# thermokoppel.net
KiCad netlist of a schematic drawn in Altium Designer
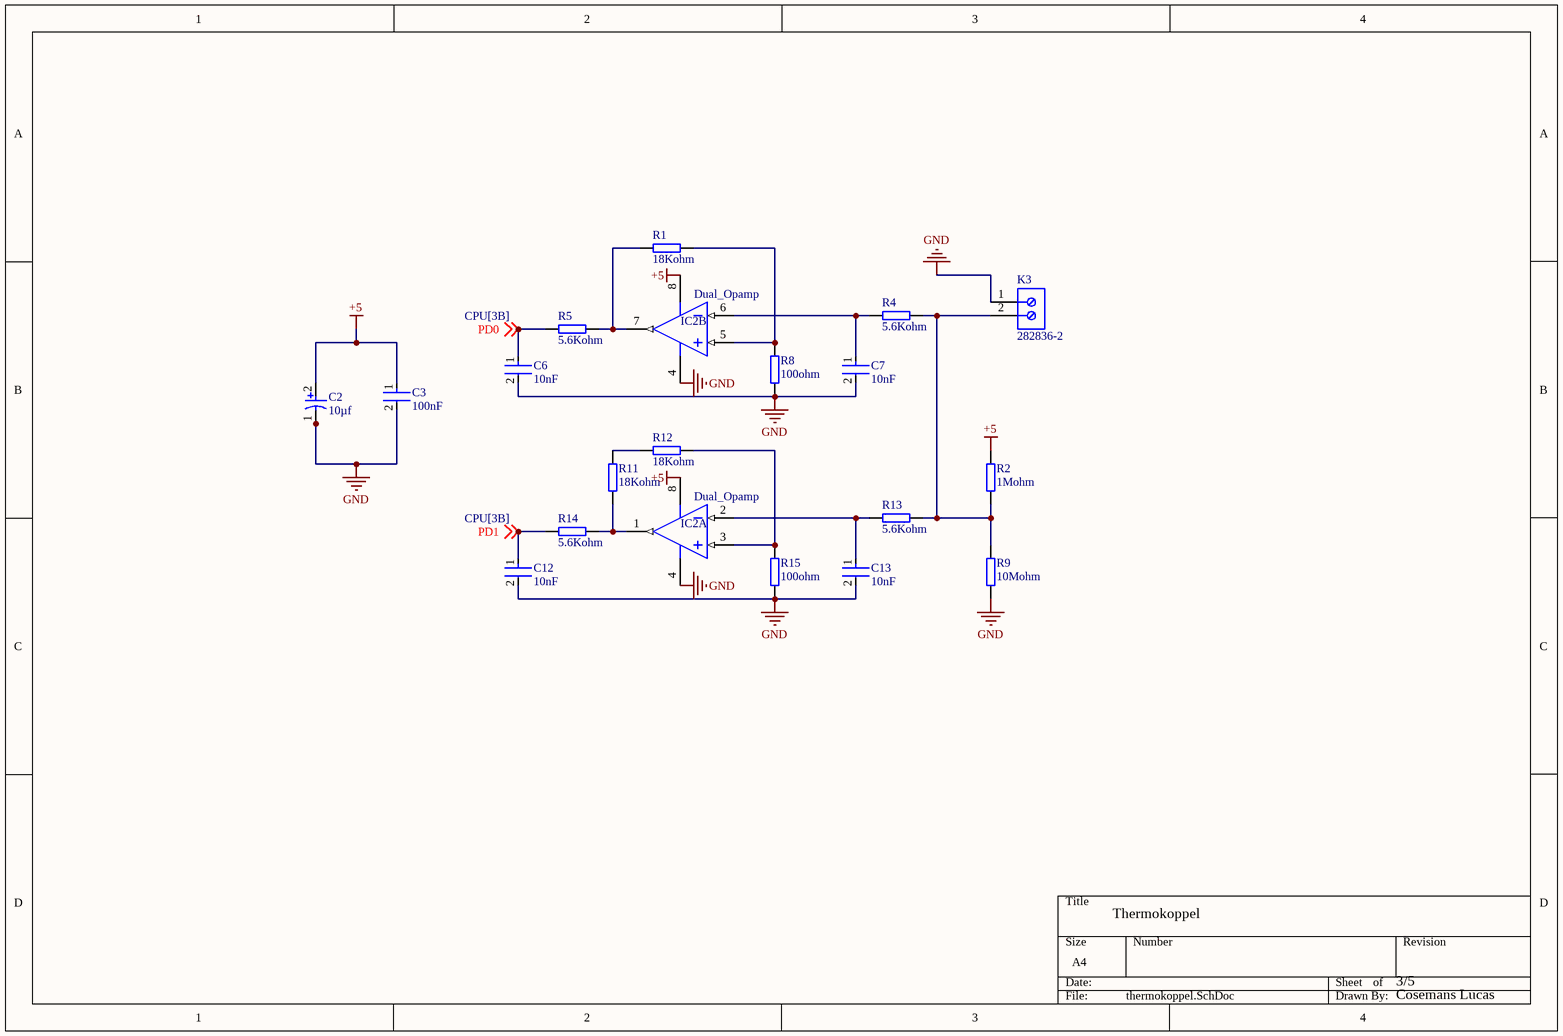
[diagram p0: thermokoppel.SchDoc]

(export (version "E")
  (design (tool "Eeschema 10.0.6"))
  (components
    (comp (ref "C2")
      (value "10µf")
      (footprint "CE_D6,3_L4,5")
      (fields (field (name "MANUFACTURER") "Panasonic"))
      (libsource (lib "Schematic_soldeerstation") (part "Capacitor_Electrolytic"))
    )
    (comp (ref "C3")
      (value "100nF")
      (footprint "CC_0805_L")
      (fields
        (field (name "MANUFACTURER") "KEMET")
        (field (name "OCTOPART") "https://octopart.com/c0805c224k5ractu-kemet-144670")
        (field (name "MANUFACTURER PART NUMBER") "C0805C224K5RACTU")
      )
      (libsource (lib "Schematic_soldeerstation") (part "Capacitor_Ceramic"))
    )
    (comp (ref "C6")
      (value "10nF")
      (footprint "CC_0805_L")
      (fields
        (field (name "MANUFACTURER") "KEMET")
        (field (name "OCTOPART") "https://octopart.com/c0805c224k5ractu-kemet-144670")
        (field (name "MANUFACTURER PART NUMBER") "C0805C224K5RACTU")
      )
      (libsource (lib "Schematic_soldeerstation") (part "Capacitor_Ceramic"))
    )
    (comp (ref "C7")
      (value "10nF")
      (footprint "CC_0805_L")
      (fields
        (field (name "MANUFACTURER") "KEMET")
        (field (name "OCTOPART") "https://octopart.com/c0805c224k5ractu-kemet-144670")
        (field (name "MANUFACTURER PART NUMBER") "C0805C224K5RACTU")
      )
      (libsource (lib "Schematic_soldeerstation") (part "Capacitor_Ceramic"))
    )
    (comp (ref "C12")
      (value "10nF")
      (footprint "CC_0805_L")
      (fields
        (field (name "MANUFACTURER") "KEMET")
        (field (name "OCTOPART") "https://octopart.com/c0805c224k5ractu-kemet-144670")
        (field (name "MANUFACTURER PART NUMBER") "C0805C224K5RACTU")
      )
      (libsource (lib "Schematic_soldeerstation") (part "Capacitor_Ceramic"))
    )
    (comp (ref "C13")
      (value "10nF")
      (footprint "CC_0805_L")
      (fields
        (field (name "MANUFACTURER") "KEMET")
        (field (name "OCTOPART") "https://octopart.com/c0805c224k5ractu-kemet-144670")
        (field (name "MANUFACTURER PART NUMBER") "C0805C224K5RACTU")
      )
      (libsource (lib "Schematic_soldeerstation") (part "Capacitor_Ceramic"))
    )
    (comp (ref "IC2")
      (value "Dual_Opamp")
      (footprint "MSOP_8_M")
      (libsource (lib "Schematic_soldeerstation") (part "Dual_Opamp"))
    )
    (comp (ref "K3")
      (value "282836-2")
      (footprint "2x1 Schroef pin TECO-282836-2_V")
      (description "Female Header, Pitch 5 mm, 1 x 2 Position, Height 10 mm, Tail Length 3.5 mm, Rohs, Bulk")
      (fields (field (name "VOLTAGE") "300V") (field (name "MANUFACTURER") "TE Connectivity"))
      (libsource (lib "Schematic_soldeerstation") (part "2x1 schroef pin"))
    )
    (comp (ref "R1")
      (value "18Kohm")
      (footprint "R_0805_M")
      (fields (field (name "MANUFACTURER") "Vishay Dale") (field (name "PART NUMBER") "CRCW08050000Z0EA"))
      (libsource (lib "Schematic_soldeerstation") (part "Resistor"))
    )
    (comp (ref "R2")
      (value "1Mohm")
      (footprint "R_0805_M")
      (fields (field (name "MANUFACTURER") "Vishay Dale") (field (name "PART NUMBER") "CRCW08050000Z0EA"))
      (libsource (lib "Schematic_soldeerstation") (part "Resistor"))
    )
    (comp (ref "R4")
      (value "5.6Kohm")
      (footprint "R_0805_M")
      (fields (field (name "MANUFACTURER") "Vishay Dale") (field (name "PART NUMBER") "CRCW08050000Z0EA"))
      (libsource (lib "Schematic_soldeerstation") (part "Resistor"))
    )
    (comp (ref "R5")
      (value "5.6Kohm")
      (footprint "R_0805_M")
      (fields (field (name "MANUFACTURER") "Vishay Dale") (field (name "PART NUMBER") "CRCW08050000Z0EA"))
      (libsource (lib "Schematic_soldeerstation") (part "Resistor"))
    )
    (comp (ref "R8")
      (value "100ohm")
      (footprint "R_0805_M")
      (fields (field (name "MANUFACTURER") "Vishay Dale") (field (name "PART NUMBER") "CRCW08050000Z0EA"))
      (libsource (lib "Schematic_soldeerstation") (part "Resistor"))
    )
    (comp (ref "R9")
      (value "10Mohm")
      (footprint "R_0805_M")
      (fields (field (name "MANUFACTURER") "Vishay Dale") (field (name "PART NUMBER") "CRCW08050000Z0EA"))
      (libsource (lib "Schematic_soldeerstation") (part "Resistor"))
    )
    (comp (ref "R11")
      (value "18Kohm")
      (footprint "R_0805_M")
      (fields (field (name "MANUFACTURER") "Vishay Dale") (field (name "PART NUMBER") "CRCW08050000Z0EA"))
      (libsource (lib "Schematic_soldeerstation") (part "Resistor"))
    )
    (comp (ref "R12")
      (value "18Kohm")
      (footprint "R_0805_M")
      (fields (field (name "MANUFACTURER") "Vishay Dale") (field (name "PART NUMBER") "CRCW08050000Z0EA"))
      (libsource (lib "Schematic_soldeerstation") (part "Resistor"))
    )
    (comp (ref "R13")
      (value "5.6Kohm")
      (footprint "R_0805_M")
      (fields (field (name "MANUFACTURER") "Vishay Dale") (field (name "PART NUMBER") "CRCW08050000Z0EA"))
      (libsource (lib "Schematic_soldeerstation") (part "Resistor"))
    )
    (comp (ref "R14")
      (value "5.6Kohm")
      (footprint "R_0805_M")
      (fields (field (name "MANUFACTURER") "Vishay Dale") (field (name "PART NUMBER") "CRCW08050000Z0EA"))
      (libsource (lib "Schematic_soldeerstation") (part "Resistor"))
    )
    (comp (ref "R15")
      (value "100ohm")
      (footprint "R_0805_M")
      (fields (field (name "MANUFACTURER") "Vishay Dale") (field (name "PART NUMBER") "CRCW08050000Z0EA"))
      (libsource (lib "Schematic_soldeerstation") (part "Resistor"))
    )
  )
  (nets
    (net (code "1") (name "+5") (class "Default")
      (node (ref "C2") (pin "2") (pinfunction "2_2") (pintype "passive"))
      (node (ref "C3") (pin "1") (pinfunction "1_1") (pintype "passive"))
      (node (ref "IC2") (pin "8") (pinfunction "VDD_8") (pintype "power_in"))
      (node (ref "R2") (pin "2") (pinfunction "2_2") (pintype "passive"))
    )
    (net (code "2") (name "GND") (class "Default")
      (node (ref "C12") (pin "2") (pinfunction "2_2") (pintype "passive"))
      (node (ref "C13") (pin "2") (pinfunction "2_2") (pintype "passive"))
      (node (ref "C2") (pin "1") (pinfunction "1_1") (pintype "passive"))
      (node (ref "C3") (pin "2") (pinfunction "2_2") (pintype "passive"))
      (node (ref "C6") (pin "2") (pinfunction "2_2") (pintype "passive"))
      (node (ref "C7") (pin "2") (pinfunction "2_2") (pintype "passive"))
      (node (ref "IC2") (pin "4") (pinfunction "VSS_4") (pintype "power_in"))
      (node (ref "K3") (pin "1") (pinfunction "1_1") (pintype "passive"))
      (node (ref "R15") (pin "1") (pinfunction "1_1") (pintype "passive"))
      (node (ref "R8") (pin "1") (pinfunction "1_1") (pintype "passive"))
      (node (ref "R9") (pin "1") (pinfunction "1_1") (pintype "passive"))
    )
    (net (code "3") (name "Net-(IC2A-VINA+)") (class "Default")
      (node (ref "IC2") (pin "3") (pinfunction "VINA+_3") (pintype "input"))
      (node (ref "R12") (pin "2") (pinfunction "2_2") (pintype "passive"))
      (node (ref "R15") (pin "2") (pinfunction "2_2") (pintype "passive"))
    )
    (net (code "4") (name "Net-(IC2A-VINA-)") (class "Default")
      (node (ref "C13") (pin "1") (pinfunction "1_1") (pintype "passive"))
      (node (ref "IC2") (pin "2") (pinfunction "VINA-_2") (pintype "input"))
      (node (ref "R13") (pin "1") (pinfunction "1_1") (pintype "passive"))
    )
    (net (code "5") (name "Net-(IC2A-VOUTA)") (class "Default")
      (node (ref "IC2") (pin "1") (pinfunction "VOUTA_1") (pintype "output"))
      (node (ref "R11") (pin "1") (pinfunction "1_1") (pintype "passive"))
      (node (ref "R14") (pin "2") (pinfunction "2_2") (pintype "passive"))
    )
    (net (code "6") (name "Net-(IC2B-VINB+)") (class "Default")
      (node (ref "IC2") (pin "5") (pinfunction "VINB+_5") (pintype "input"))
      (node (ref "R1") (pin "2") (pinfunction "2_2") (pintype "passive"))
      (node (ref "R8") (pin "2") (pinfunction "2_2") (pintype "passive"))
    )
    (net (code "7") (name "Net-(IC2B-VINB-)") (class "Default")
      (node (ref "C7") (pin "1") (pinfunction "1_1") (pintype "passive"))
      (node (ref "IC2") (pin "6") (pinfunction "VINB-_6") (pintype "input"))
      (node (ref "R4") (pin "1") (pinfunction "1_1") (pintype "passive"))
    )
    (net (code "8") (name "Net-(IC2B-VOUTB)") (class "Default")
      (node (ref "IC2") (pin "7") (pinfunction "VOUTB_7") (pintype "output"))
      (node (ref "R1") (pin "1") (pinfunction "1_1") (pintype "passive"))
      (node (ref "R5") (pin "2") (pinfunction "2_2") (pintype "passive"))
    )
    (net (code "9") (name "Net-(K3-Pad2)") (class "Default")
      (node (ref "K3") (pin "2") (pinfunction "2_2") (pintype "passive"))
      (node (ref "R13") (pin "2") (pinfunction "2_2") (pintype "passive"))
      (node (ref "R2") (pin "1") (pinfunction "1_1") (pintype "passive"))
      (node (ref "R4") (pin "2") (pinfunction "2_2") (pintype "passive"))
      (node (ref "R9") (pin "2") (pinfunction "2_2") (pintype "passive"))
    )
    (net (code "10") (name "Net-(R11-Pad2)") (class "Default")
      (node (ref "R11") (pin "2") (pinfunction "2_2") (pintype "passive"))
      (node (ref "R12") (pin "1") (pinfunction "1_1") (pintype "passive"))
    )
    (net (code "11") (name "PD0") (class "Default")
      (node (ref "C6") (pin "1") (pinfunction "1_1") (pintype "passive"))
      (node (ref "R5") (pin "1") (pinfunction "1_1") (pintype "passive"))
    )
    (net (code "12") (name "PD1") (class "Default")
      (node (ref "C12") (pin "1") (pinfunction "1_1") (pintype "passive"))
      (node (ref "R14") (pin "1") (pinfunction "1_1") (pintype "passive"))
    )
  )
)
